# BI2.net
KiCad netlist of a schematic drawn in Altium Designer
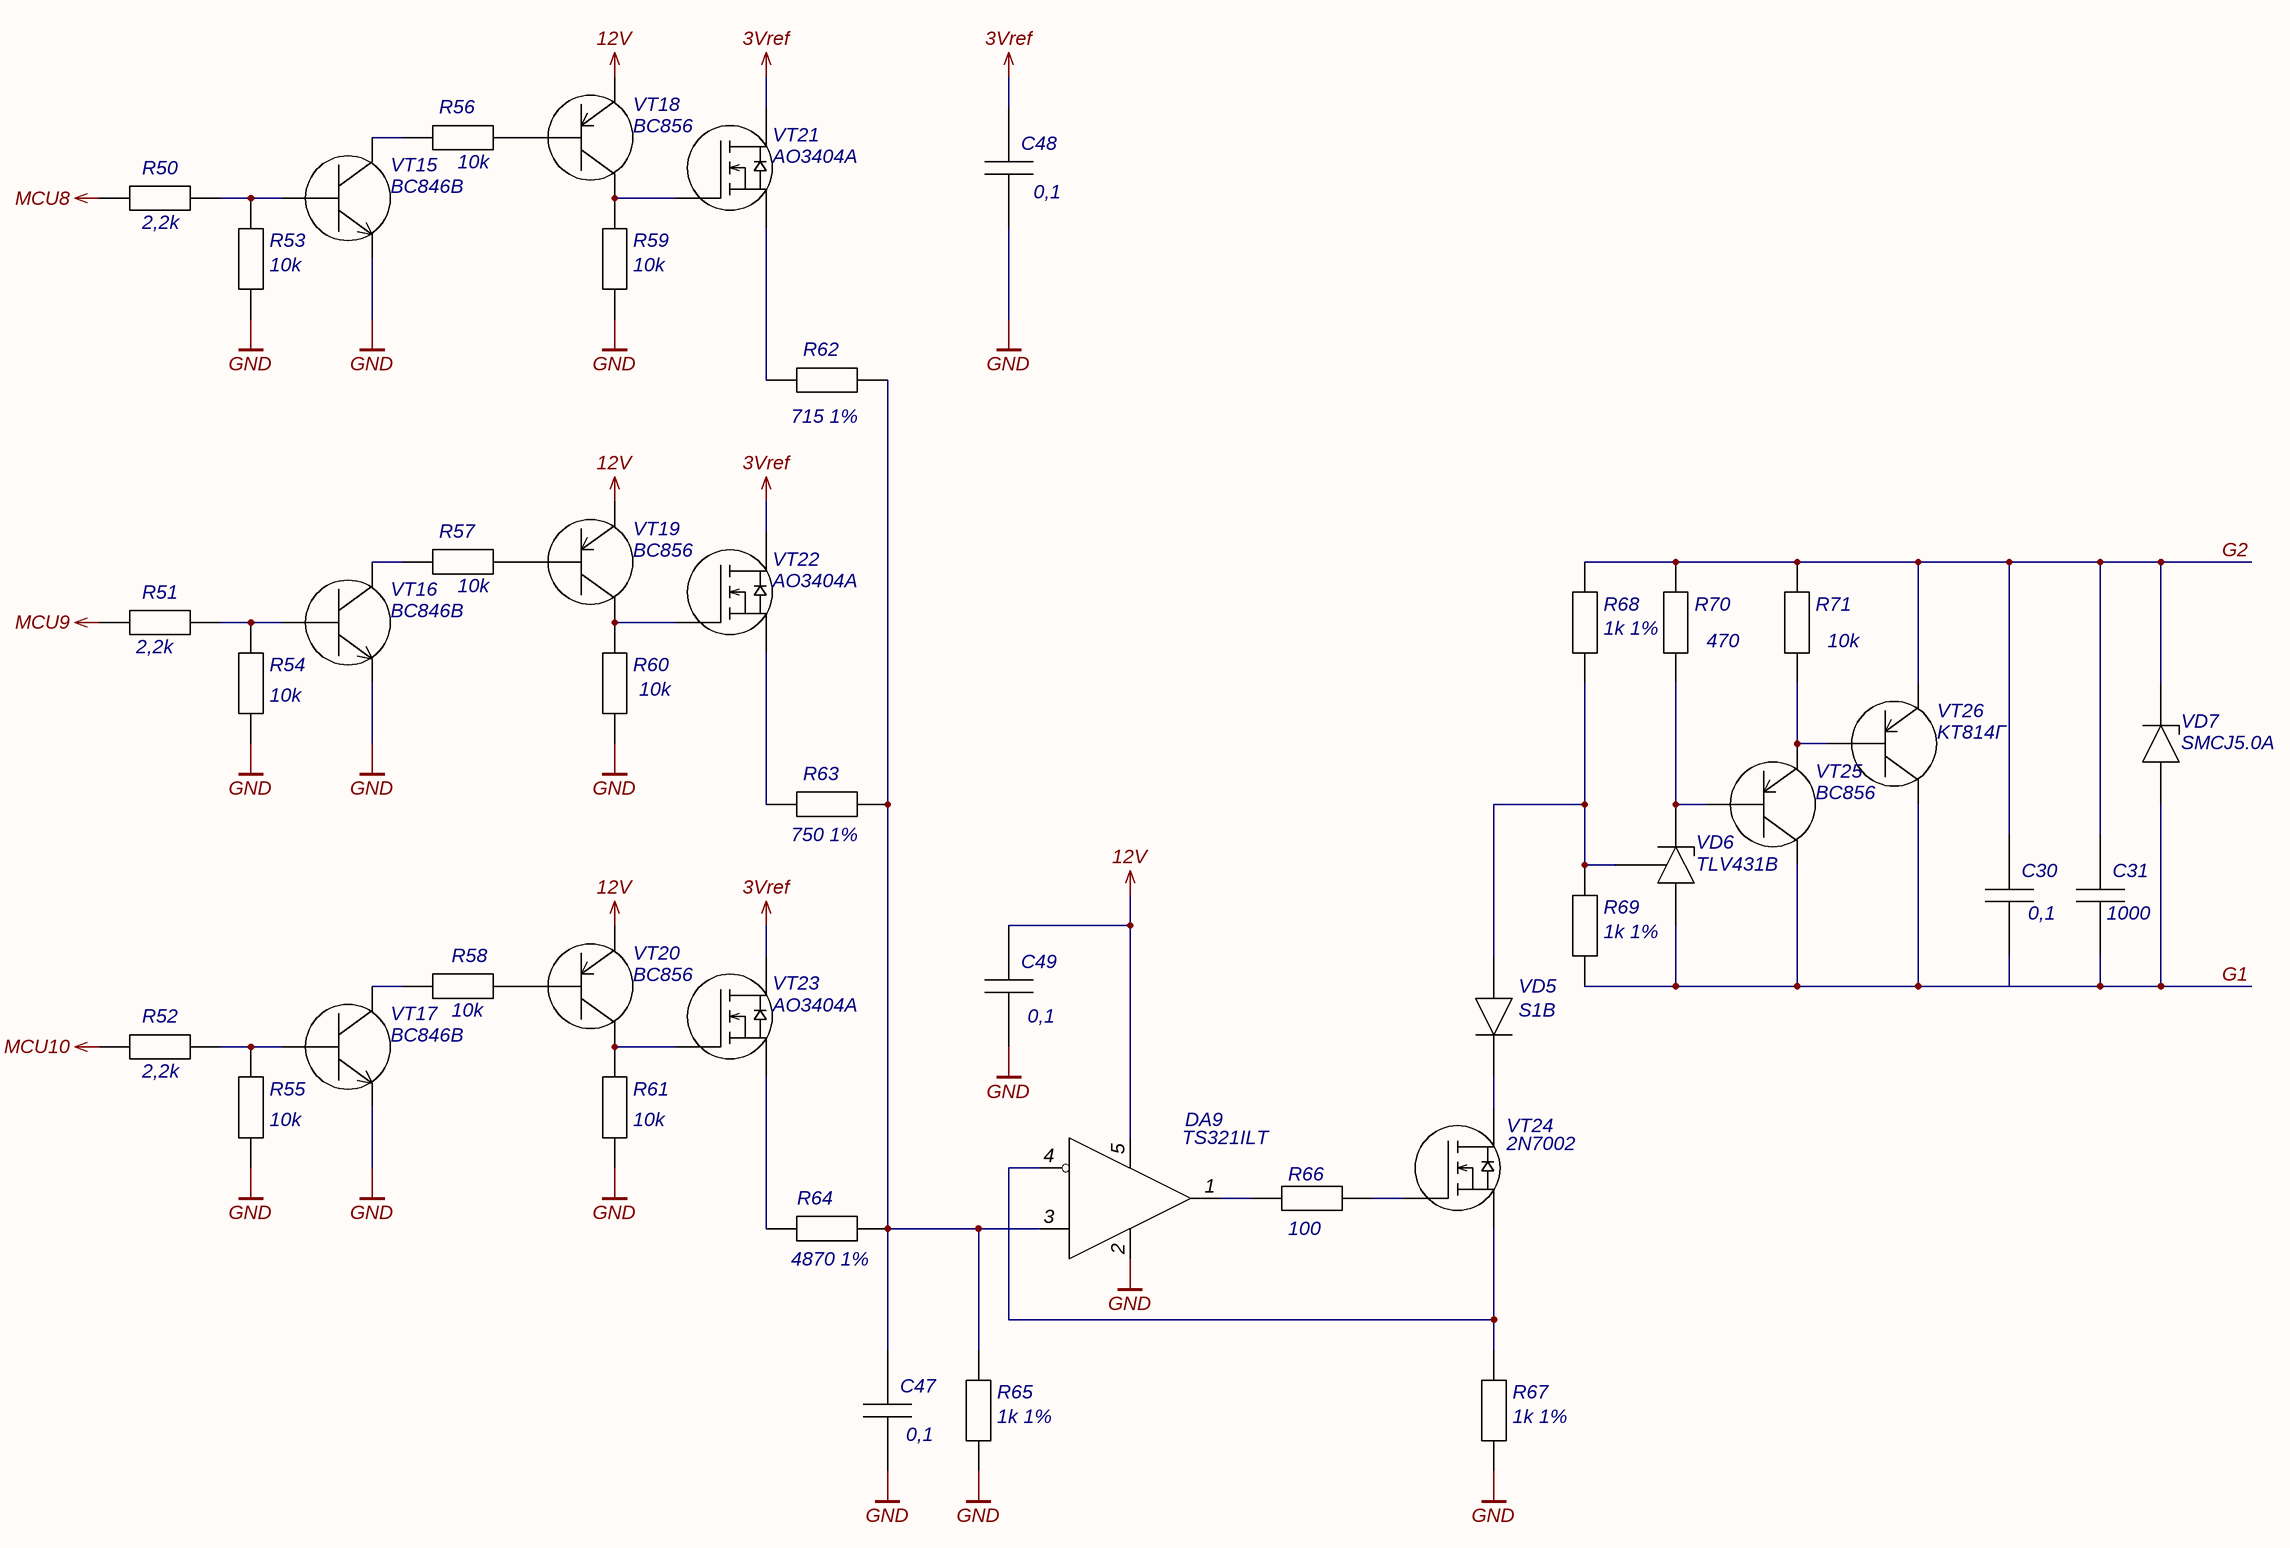
[diagram p0: BI2.SchDoc]

(export (version "E")
  (design (tool "Eeschema 10.0.6"))
  (components
    (comp (ref "C30")
      (value "0,1")
      (footprint "C0603")
      (description "Чип-конденсатор")
      (libsource (lib "Passive") (part "Chip Capasitor"))
    )
    (comp (ref "C31")
      (value "1000")
      (footprint "C0603")
      (description "Чип-конденсатор")
      (libsource (lib "Passive") (part "Chip Capasitor"))
    )
    (comp (ref "C47")
      (value "0,1")
      (footprint "C0603")
      (description "Чип-конденсатор")
      (libsource (lib "Passive") (part "Chip Capasitor"))
    )
    (comp (ref "C48")
      (value "0,1")
      (footprint "C0603")
      (description "Чип-конденсатор")
      (libsource (lib "Passive") (part "Chip Capasitor"))
    )
    (comp (ref "C49")
      (value "0,1")
      (footprint "C0603")
      (description "Чип-конденсатор")
      (libsource (lib "Passive") (part "Chip Capasitor"))
    )
    (comp (ref "DA9")
      (value "TS321ILT")
      (footprint "SOT-23-5")
      (description "1х Операционный усилитель")
      (libsource (lib "Schlib") (part "TS321ILT"))
    )
    (comp (ref "R50")
      (value "2,2k")
      (footprint "R0603")
      (description "Чип-резистор")
      (libsource (lib "Passive") (part "Chip Resistor"))
    )
    (comp (ref "R51")
      (value "2,2k")
      (footprint "R0603")
      (description "Чип-резистор")
      (libsource (lib "Passive") (part "Chip Resistor"))
    )
    (comp (ref "R52")
      (value "2,2k")
      (footprint "R0603")
      (description "Чип-резистор")
      (libsource (lib "Passive") (part "Chip Resistor"))
    )
    (comp (ref "R53")
      (value "10k")
      (footprint "R0603")
      (description "Чип-резистор")
      (libsource (lib "") (part "Chip Resistor_1"))
    )
    (comp (ref "R54")
      (value "10k")
      (footprint "R0603")
      (description "Чип-резистор")
      (libsource (lib "") (part "Chip Resistor_1"))
    )
    (comp (ref "R55")
      (value "10k")
      (footprint "R0603")
      (description "Чип-резистор")
      (libsource (lib "") (part "Chip Resistor_1"))
    )
    (comp (ref "R56")
      (value "10k")
      (footprint "R0603")
      (description "Чип-резистор")
      (libsource (lib "Passive") (part "Chip Resistor"))
    )
    (comp (ref "R57")
      (value "10k")
      (footprint "R0603")
      (description "Чип-резистор")
      (libsource (lib "Passive") (part "Chip Resistor"))
    )
    (comp (ref "R58")
      (value "10k")
      (footprint "R0603")
      (description "Чип-резистор")
      (libsource (lib "Passive") (part "Chip Resistor"))
    )
    (comp (ref "R59")
      (value "10k")
      (footprint "R0603")
      (description "Чип-резистор")
      (libsource (lib "") (part "Chip Resistor_1"))
    )
    (comp (ref "R60")
      (value "10k")
      (footprint "R0603")
      (description "Чип-резистор")
      (libsource (lib "") (part "Chip Resistor_1"))
    )
    (comp (ref "R61")
      (value "10k")
      (footprint "R0603")
      (description "Чип-резистор")
      (libsource (lib "") (part "Chip Resistor_1"))
    )
    (comp (ref "R62")
      (value "715 1%")
      (footprint "R0603")
      (description "Чип-резистор")
      (fields (field (name "PARTNUMBER") "RC0603FR-07715RL"))
      (libsource (lib "Passive") (part "Chip Resistor"))
    )
    (comp (ref "R63")
      (value "750 1%")
      (footprint "R0603")
      (description "Чип-резистор")
      (fields (field (name "PARTNUMBER") "RC0603FR-07750RL"))
      (libsource (lib "Passive") (part "Chip Resistor"))
    )
    (comp (ref "R64")
      (value "4870 1%")
      (footprint "R0603")
      (description "Чип-резистор")
      (fields (field (name "PARTNUMBER") "RC0603FR-074K87L"))
      (libsource (lib "Passive") (part "Chip Resistor"))
    )
    (comp (ref "R65")
      (value "1k 1%")
      (footprint "R0603")
      (description "Чип-резистор")
      (fields (field (name "PARTNUMBER") "CRCW06031K00FKEAC"))
      (libsource (lib "") (part "Chip Resistor_1"))
    )
    (comp (ref "R66")
      (value "100")
      (footprint "R0603")
      (description "Чип-резистор")
      (libsource (lib "Passive") (part "Chip Resistor"))
    )
    (comp (ref "R67")
      (value "1k 1%")
      (footprint "R0603")
      (description "Чип-резистор")
      (fields (field (name "PARTNUMBER") "CRCW06031K00FKEAC"))
      (libsource (lib "") (part "Chip Resistor_1"))
    )
    (comp (ref "R68")
      (value "1k 1%")
      (footprint "R0603")
      (description "Чип-резистор")
      (fields (field (name "PARTNUMBER") "CRCW06031K00FKEAC"))
      (libsource (lib "") (part "Chip Resistor_1"))
    )
    (comp (ref "R69")
      (value "1k 1%")
      (footprint "R0603")
      (description "Чип-резистор")
      (fields (field (name "PARTNUMBER") "CRCW06031K00FKEAC"))
      (libsource (lib "") (part "Chip Resistor_1"))
    )
    (comp (ref "R70")
      (value "470")
      (footprint "R0603")
      (description "Чип-резистор")
      (libsource (lib "") (part "Chip Resistor_1"))
    )
    (comp (ref "R71")
      (value "10k")
      (footprint "R0603")
      (description "Чип-резистор")
      (libsource (lib "") (part "Chip Resistor_1"))
    )
    (comp (ref "VD5")
      (value "S1B")
      (footprint "DO-214AC")
      (description "Диод выпрямительный, 100В")
      (fields (field (name "MANUFACTURER") "Diotec Semiconductor"))
      (libsource (lib "Schlib") (part "S1B"))
    )
    (comp (ref "VD6")
      (value "TLV431B")
      (footprint "SOT-23")
      (description "Стабилитрон регулируемый, 6В")
      (fields (field (name "MANUFACTURER") "Texas Instruments"))
      (libsource (lib "Schlib") (part "TLV431B"))
    )
    (comp (ref "VD7")
      (value "SMCJ5.0A")
      (footprint "DO-214AB")
      (description "Защитный диод, 5В")
      (fields (field (name "MANUFACTURER") "UTD Semiconductor Co.,Ltd"))
      (libsource (lib "Schlib") (part "SMCJ5.0A"))
    )
    (comp (ref "VT15")
      (value "BC846B")
      (footprint "SOT-23")
      (description "Транзистор биполярный NPN, 65В")
      (fields (field (name "MANUFACTURER") "Nexperia B.V."))
      (libsource (lib "Schlib") (part "BC846B"))
    )
    (comp (ref "VT16")
      (value "BC846B")
      (footprint "SOT-23")
      (description "Транзистор биполярный NPN, 65В")
      (fields (field (name "MANUFACTURER") "Nexperia B.V."))
      (libsource (lib "Schlib") (part "BC846B"))
    )
    (comp (ref "VT17")
      (value "BC846B")
      (footprint "SOT-23")
      (description "Транзистор биполярный NPN, 65В")
      (fields (field (name "MANUFACTURER") "Nexperia B.V."))
      (libsource (lib "Schlib") (part "BC846B"))
    )
    (comp (ref "VT18")
      (value "BC856")
      (footprint "SOT-23")
      (description "Транзистор биполярный PNP, 65В")
      (fields (field (name "MANUFACTURER") "Nexperia"))
      (libsource (lib "Schlib") (part "BC856"))
    )
    (comp (ref "VT19")
      (value "BC856")
      (footprint "SOT-23")
      (description "Транзистор биполярный PNP, 65В")
      (fields (field (name "MANUFACTURER") "Nexperia"))
      (libsource (lib "Schlib") (part "BC856"))
    )
    (comp (ref "VT20")
      (value "BC856")
      (footprint "SOT-23")
      (description "Транзистор биполярный PNP, 65В")
      (fields (field (name "MANUFACTURER") "Nexperia"))
      (libsource (lib "Schlib") (part "BC856"))
    )
    (comp (ref "VT21")
      (value "AO3404A")
      (footprint "SOT-23")
      (description "Транзистор MOSFET N-канал, 30В")
      (fields (field (name "MANUFACTURER") "UTD Semiconductor Co.,Ltd"))
      (libsource (lib "Schlib") (part "AO3404A"))
    )
    (comp (ref "VT22")
      (value "AO3404A")
      (footprint "SOT-23")
      (description "Транзистор MOSFET N-канал, 30В")
      (fields (field (name "MANUFACTURER") "UTD Semiconductor Co.,Ltd"))
      (libsource (lib "Schlib") (part "AO3404A"))
    )
    (comp (ref "VT23")
      (value "AO3404A")
      (footprint "SOT-23")
      (description "Транзистор MOSFET N-канал, 30В")
      (fields (field (name "MANUFACTURER") "UTD Semiconductor Co.,Ltd"))
      (libsource (lib "Schlib") (part "AO3404A"))
    )
    (comp (ref "VT24")
      (value "2N7002")
      (footprint "SOT-23")
      (description "Транзистор MOSFET N-канал, 60В")
      (fields (field (name "MANUFACTURER") "UTD Semiconductor Co."))
      (libsource (lib "Schlib") (part "2N7002"))
    )
    (comp (ref "VT25")
      (value "BC856")
      (footprint "SOT-23")
      (description "Транзистор биполярный PNP, 65В")
      (fields (field (name "MANUFACTURER") "Nexperia"))
      (libsource (lib "Schlib") (part "BC856"))
    )
    (comp (ref "VT26")
      (value "KT814Г")
      (footprint "TO-126")
      (description "Транзистор биполярный PNP, 100В")
      (fields (field (name "MANUFACTURER") "АО «ГРУППА КРЕМНИЙ ЭЛ»"))
      (libsource (lib "Schlib") (part "KT814Г"))
    )
  )
  (nets
    (net (code "1") (name "/G1") (class "Default")
      (node (ref "C30") (pin "1") (pinfunction "1_1") (pintype "passive"))
      (node (ref "C31") (pin "1") (pinfunction "1_1") (pintype "passive"))
      (node (ref "R69") (pin "1") (pinfunction "1_1") (pintype "passive"))
      (node (ref "VD6") (pin "1") (pinfunction "1_1") (pintype "passive"))
      (node (ref "VD7") (pin "1") (pinfunction "1_1") (pintype "passive"))
      (node (ref "VT25") (pin "2") (pinfunction "2_2") (pintype "passive"))
      (node (ref "VT26") (pin "2") (pinfunction "2_2") (pintype "passive"))
    )
    (net (code "2") (name "/G2") (class "Default")
      (node (ref "C30") (pin "2") (pinfunction "2_2") (pintype "passive"))
      (node (ref "C31") (pin "2") (pinfunction "2_2") (pintype "passive"))
      (node (ref "R68") (pin "2") (pinfunction "2_2") (pintype "passive"))
      (node (ref "R70") (pin "2") (pinfunction "2_2") (pintype "passive"))
      (node (ref "R71") (pin "2") (pinfunction "2_2") (pintype "passive"))
      (node (ref "VD7") (pin "2") (pinfunction "2_2") (pintype "passive"))
      (node (ref "VT26") (pin "1") (pinfunction "1_1") (pintype "passive"))
    )
    (net (code "3") (name "3Vref") (class "Default")
      (node (ref "C48") (pin "2") (pinfunction "2_2") (pintype "passive"))
      (node (ref "VT21") (pin "2") (pinfunction "D_2") (pintype "passive"))
      (node (ref "VT22") (pin "2") (pinfunction "D_2") (pintype "passive"))
      (node (ref "VT23") (pin "2") (pinfunction "D_2") (pintype "passive"))
    )
    (net (code "4") (name "12V") (class "Default")
      (node (ref "C49") (pin "2") (pinfunction "2_2") (pintype "passive"))
      (node (ref "DA9") (pin "5") (pinfunction "Vcc_5") (pintype "passive"))
      (node (ref "VT18") (pin "1") (pinfunction "1_1") (pintype "passive"))
      (node (ref "VT19") (pin "1") (pinfunction "1_1") (pintype "passive"))
      (node (ref "VT20") (pin "1") (pinfunction "1_1") (pintype "passive"))
    )
    (net (code "5") (name "GND") (class "Default")
      (node (ref "C47") (pin "1") (pinfunction "1_1") (pintype "passive"))
      (node (ref "C48") (pin "1") (pinfunction "1_1") (pintype "passive"))
      (node (ref "C49") (pin "1") (pinfunction "1_1") (pintype "passive"))
      (node (ref "DA9") (pin "2") (pinfunction "GND_2") (pintype "passive"))
      (node (ref "R53") (pin "1") (pinfunction "1_1") (pintype "passive"))
      (node (ref "R54") (pin "1") (pinfunction "1_1") (pintype "passive"))
      (node (ref "R55") (pin "1") (pinfunction "1_1") (pintype "passive"))
      (node (ref "R59") (pin "1") (pinfunction "1_1") (pintype "passive"))
      (node (ref "R60") (pin "1") (pinfunction "1_1") (pintype "passive"))
      (node (ref "R61") (pin "1") (pinfunction "1_1") (pintype "passive"))
      (node (ref "R65") (pin "1") (pinfunction "1_1") (pintype "passive"))
      (node (ref "R67") (pin "1") (pinfunction "1_1") (pintype "passive"))
      (node (ref "VT15") (pin "2") (pinfunction "E_2") (pintype "passive"))
      (node (ref "VT16") (pin "2") (pinfunction "E_2") (pintype "passive"))
      (node (ref "VT17") (pin "2") (pinfunction "E_2") (pintype "passive"))
    )
    (net (code "6") (name "MCU8") (class "Default")
      (node (ref "R50") (pin "1") (pinfunction "1_1") (pintype "passive"))
    )
    (net (code "7") (name "MCU9") (class "Default")
      (node (ref "R51") (pin "1") (pinfunction "1_1") (pintype "passive"))
    )
    (net (code "8") (name "MCU10") (class "Default")
      (node (ref "R52") (pin "1") (pinfunction "1_1") (pintype "passive"))
    )
    (net (code "9") (name "Net-(DA9-+)") (class "Default")
      (node (ref "C47") (pin "2") (pinfunction "2_2") (pintype "passive"))
      (node (ref "DA9") (pin "3") (pinfunction "+_3") (pintype "passive"))
      (node (ref "R62") (pin "2") (pinfunction "2_2") (pintype "passive"))
      (node (ref "R63") (pin "2") (pinfunction "2_2") (pintype "passive"))
      (node (ref "R64") (pin "2") (pinfunction "2_2") (pintype "passive"))
      (node (ref "R65") (pin "2") (pinfunction "2_2") (pintype "passive"))
    )
    (net (code "10") (name "Net-(DA9--)") (class "Default")
      (node (ref "DA9") (pin "4") (pinfunction "-_4") (pintype "passive"))
      (node (ref "R67") (pin "2") (pinfunction "2_2") (pintype "passive"))
      (node (ref "VT24") (pin "3") (pinfunction "S_3") (pintype "passive"))
    )
    (net (code "11") (name "Net-(DA9-OUT)") (class "Default")
      (node (ref "DA9") (pin "1") (pinfunction "OUT_1") (pintype "passive"))
      (node (ref "R66") (pin "1") (pinfunction "1_1") (pintype "passive"))
    )
    (net (code "12") (name "Net-(R56-Pad2)") (class "Default")
      (node (ref "R56") (pin "2") (pinfunction "2_2") (pintype "passive"))
      (node (ref "VT18") (pin "3") (pinfunction "3_3") (pintype "passive"))
    )
    (net (code "13") (name "Net-(R57-Pad2)") (class "Default")
      (node (ref "R57") (pin "2") (pinfunction "2_2") (pintype "passive"))
      (node (ref "VT19") (pin "3") (pinfunction "3_3") (pintype "passive"))
    )
    (net (code "14") (name "Net-(R58-Pad2)") (class "Default")
      (node (ref "R58") (pin "2") (pinfunction "2_2") (pintype "passive"))
      (node (ref "VT20") (pin "3") (pinfunction "3_3") (pintype "passive"))
    )
    (net (code "15") (name "Net-(R68-Pad1)") (class "Default")
      (node (ref "R68") (pin "1") (pinfunction "1_1") (pintype "passive"))
      (node (ref "R69") (pin "2") (pinfunction "2_2") (pintype "passive"))
      (node (ref "VD5") (pin "1") (pinfunction "1_1") (pintype "passive"))
      (node (ref "VD6") (pin "3") (pinfunction "3_3") (pintype "passive"))
    )
    (net (code "16") (name "Net-(R70-Pad1)") (class "Default")
      (node (ref "R70") (pin "1") (pinfunction "1_1") (pintype "passive"))
      (node (ref "VD6") (pin "2") (pinfunction "2_2") (pintype "passive"))
      (node (ref "VT25") (pin "3") (pinfunction "3_3") (pintype "passive"))
    )
    (net (code "17") (name "Net-(R71-Pad1)") (class "Default")
      (node (ref "R71") (pin "1") (pinfunction "1_1") (pintype "passive"))
      (node (ref "VT25") (pin "1") (pinfunction "1_1") (pintype "passive"))
      (node (ref "VT26") (pin "3") (pinfunction "3_3") (pintype "passive"))
    )
    (net (code "18") (name "Net-(VT15-B)") (class "Default")
      (node (ref "R50") (pin "2") (pinfunction "2_2") (pintype "passive"))
      (node (ref "R53") (pin "2") (pinfunction "2_2") (pintype "passive"))
      (node (ref "VT15") (pin "1") (pinfunction "B_1") (pintype "passive"))
    )
    (net (code "19") (name "Net-(VT15-C)") (class "Default")
      (node (ref "R56") (pin "1") (pinfunction "1_1") (pintype "passive"))
      (node (ref "VT15") (pin "3") (pinfunction "C_3") (pintype "passive"))
    )
    (net (code "20") (name "Net-(VT16-B)") (class "Default")
      (node (ref "R51") (pin "2") (pinfunction "2_2") (pintype "passive"))
      (node (ref "R54") (pin "2") (pinfunction "2_2") (pintype "passive"))
      (node (ref "VT16") (pin "1") (pinfunction "B_1") (pintype "passive"))
    )
    (net (code "21") (name "Net-(VT16-C)") (class "Default")
      (node (ref "R57") (pin "1") (pinfunction "1_1") (pintype "passive"))
      (node (ref "VT16") (pin "3") (pinfunction "C_3") (pintype "passive"))
    )
    (net (code "22") (name "Net-(VT17-B)") (class "Default")
      (node (ref "R52") (pin "2") (pinfunction "2_2") (pintype "passive"))
      (node (ref "R55") (pin "2") (pinfunction "2_2") (pintype "passive"))
      (node (ref "VT17") (pin "1") (pinfunction "B_1") (pintype "passive"))
    )
    (net (code "23") (name "Net-(VT17-C)") (class "Default")
      (node (ref "R58") (pin "1") (pinfunction "1_1") (pintype "passive"))
      (node (ref "VT17") (pin "3") (pinfunction "C_3") (pintype "passive"))
    )
    (net (code "24") (name "Net-(VT21-G)") (class "Default")
      (node (ref "R59") (pin "2") (pinfunction "2_2") (pintype "passive"))
      (node (ref "VT18") (pin "2") (pinfunction "2_2") (pintype "passive"))
      (node (ref "VT21") (pin "1") (pinfunction "G_1") (pintype "passive"))
    )
    (net (code "25") (name "Net-(VT21-S)") (class "Default")
      (node (ref "R62") (pin "1") (pinfunction "1_1") (pintype "passive"))
      (node (ref "VT21") (pin "3") (pinfunction "S_3") (pintype "passive"))
    )
    (net (code "26") (name "Net-(VT22-G)") (class "Default")
      (node (ref "R60") (pin "2") (pinfunction "2_2") (pintype "passive"))
      (node (ref "VT19") (pin "2") (pinfunction "2_2") (pintype "passive"))
      (node (ref "VT22") (pin "1") (pinfunction "G_1") (pintype "passive"))
    )
    (net (code "27") (name "Net-(VT22-S)") (class "Default")
      (node (ref "R63") (pin "1") (pinfunction "1_1") (pintype "passive"))
      (node (ref "VT22") (pin "3") (pinfunction "S_3") (pintype "passive"))
    )
    (net (code "28") (name "Net-(VT23-G)") (class "Default")
      (node (ref "R61") (pin "2") (pinfunction "2_2") (pintype "passive"))
      (node (ref "VT20") (pin "2") (pinfunction "2_2") (pintype "passive"))
      (node (ref "VT23") (pin "1") (pinfunction "G_1") (pintype "passive"))
    )
    (net (code "29") (name "Net-(VT23-S)") (class "Default")
      (node (ref "R64") (pin "1") (pinfunction "1_1") (pintype "passive"))
      (node (ref "VT23") (pin "3") (pinfunction "S_3") (pintype "passive"))
    )
    (net (code "30") (name "Net-(VT24-D)") (class "Default")
      (node (ref "VD5") (pin "2") (pinfunction "2_2") (pintype "passive"))
      (node (ref "VT24") (pin "2") (pinfunction "D_2") (pintype "passive"))
    )
    (net (code "31") (name "Net-(VT24-G)") (class "Default")
      (node (ref "R66") (pin "2") (pinfunction "2_2") (pintype "passive"))
      (node (ref "VT24") (pin "1") (pinfunction "G_1") (pintype "passive"))
    )
  )
)
